# BPSKModulator.net
KiCad netlist of a schematic drawn in EAGLE
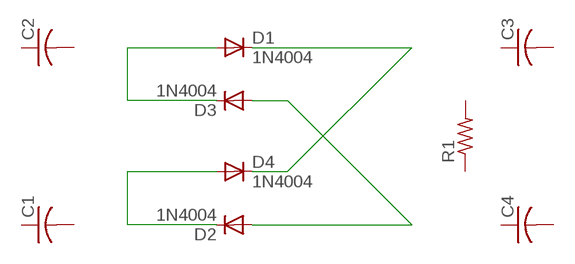
[diagram p0: schematic, sheet 1]

(export (version "E")
  (design (tool "Eeschema 10.0.6"))
  (components
    (comp (ref "C1")
      (value "C-USC0603")
      (footprint "eagle-import:C0603")
      (libsource (lib "eagle-import") (part "C-USC0603"))
    )
    (comp (ref "C2")
      (value "C-USC0603")
      (footprint "eagle-import:C0603")
      (libsource (lib "eagle-import") (part "C-USC0603"))
    )
    (comp (ref "C3")
      (value "C-USC0603")
      (footprint "eagle-import:C0603")
      (libsource (lib "eagle-import") (part "C-USC0603"))
    )
    (comp (ref "C4")
      (value "C-USC0603")
      (footprint "eagle-import:C0603")
      (libsource (lib "eagle-import") (part "C-USC0603"))
    )
    (comp (ref "D1")
      (value "1N4004")
      (footprint "eagle-import:DO41-10")
      (libsource (lib "eagle-import") (part "1N4004"))
    )
    (comp (ref "D2")
      (value "1N4004")
      (footprint "eagle-import:DO41-10")
      (libsource (lib "eagle-import") (part "1N4004"))
    )
    (comp (ref "D3")
      (value "1N4004")
      (footprint "eagle-import:DO41-10")
      (libsource (lib "eagle-import") (part "1N4004"))
    )
    (comp (ref "D4")
      (value "1N4004")
      (footprint "eagle-import:DO41-10")
      (libsource (lib "eagle-import") (part "1N4004"))
    )
    (comp (ref "R1")
      (value "R-US_R0603")
      (footprint "eagle-import:R0603")
      (libsource (lib "eagle-import") (part "R-US_R0603"))
    )
  )
  (nets
    (net (code "1") (name "Net-(D1-PadA)") (class "Default")
      (node (ref "D1") (pin "A") (pinfunction "A_A") (pintype "passive"))
      (node (ref "D3") (pin "C") (pinfunction "C_C") (pintype "passive"))
    )
    (net (code "2") (name "Net-(D1-PadC)") (class "Default")
      (node (ref "D1") (pin "C") (pinfunction "C_C") (pintype "passive"))
      (node (ref "D4") (pin "C") (pinfunction "C_C") (pintype "passive"))
    )
    (net (code "3") (name "Net-(D2-PadA)") (class "Default")
      (node (ref "D2") (pin "A") (pinfunction "A_A") (pintype "passive"))
      (node (ref "D3") (pin "A") (pinfunction "A_A") (pintype "passive"))
    )
    (net (code "4") (name "Net-(D2-PadC)") (class "Default")
      (node (ref "D2") (pin "C") (pinfunction "C_C") (pintype "passive"))
      (node (ref "D4") (pin "A") (pinfunction "A_A") (pintype "passive"))
    )
    (net (code "5") (name "unconnected-(C1-Pad1)") (class "Default")
      (node (ref "C1") (pin "1") (pinfunction "1_1") (pintype "passive"))
    )
    (net (code "6") (name "unconnected-(C1-Pad2)") (class "Default")
      (node (ref "C1") (pin "2") (pinfunction "2_2") (pintype "passive"))
    )
    (net (code "7") (name "unconnected-(C2-Pad1)") (class "Default")
      (node (ref "C2") (pin "1") (pinfunction "1_1") (pintype "passive"))
    )
    (net (code "8") (name "unconnected-(C2-Pad2)") (class "Default")
      (node (ref "C2") (pin "2") (pinfunction "2_2") (pintype "passive"))
    )
    (net (code "9") (name "unconnected-(C3-Pad1)") (class "Default")
      (node (ref "C3") (pin "1") (pinfunction "1_1") (pintype "passive"))
    )
    (net (code "10") (name "unconnected-(C3-Pad2)") (class "Default")
      (node (ref "C3") (pin "2") (pinfunction "2_2") (pintype "passive"))
    )
    (net (code "11") (name "unconnected-(C4-Pad1)") (class "Default")
      (node (ref "C4") (pin "1") (pinfunction "1_1") (pintype "passive"))
    )
    (net (code "12") (name "unconnected-(C4-Pad2)") (class "Default")
      (node (ref "C4") (pin "2") (pinfunction "2_2") (pintype "passive"))
    )
    (net (code "13") (name "unconnected-(R1-Pad1)") (class "Default")
      (node (ref "R1") (pin "1") (pinfunction "1_1") (pintype "passive"))
    )
    (net (code "14") (name "unconnected-(R1-Pad2)") (class "Default")
      (node (ref "R1") (pin "2") (pinfunction "2_2") (pintype "passive"))
    )
  )
)
